# MSDriver_Ver2_0.net
KiCad netlist of a schematic drawn in EasyEDA Pro
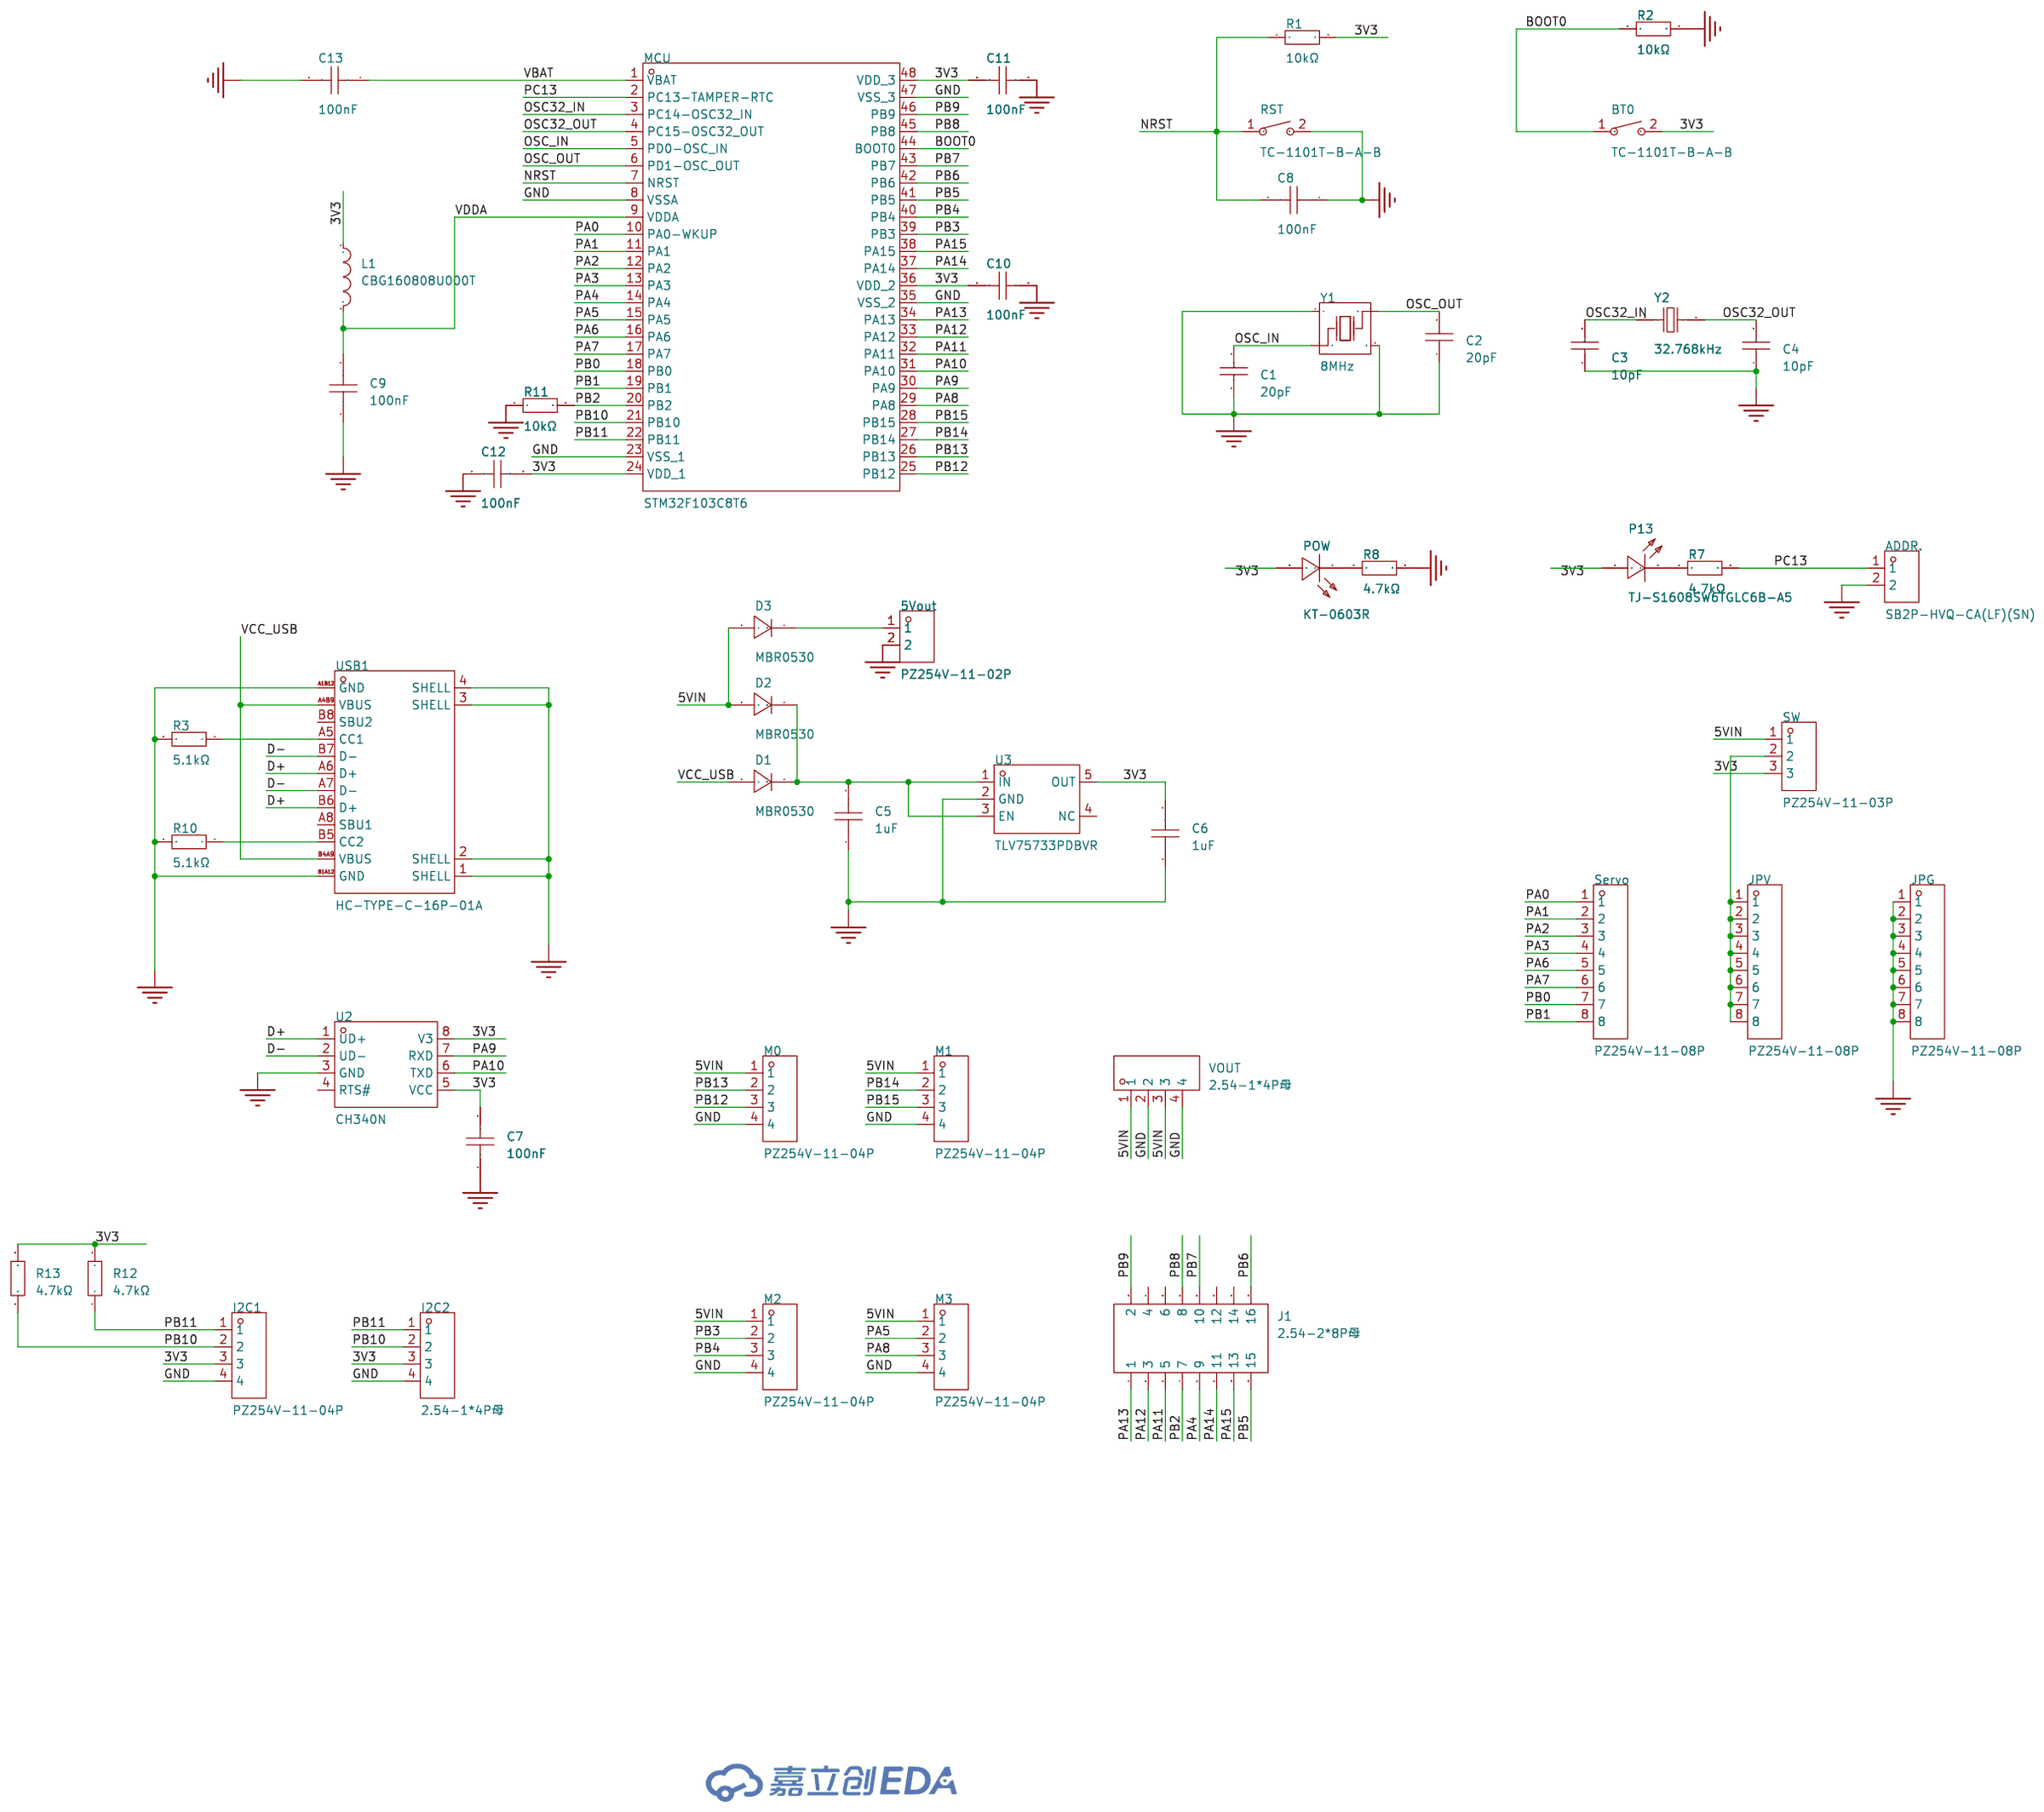
[diagram p0: schematic sheet]

(export (version "E")
  (design (tool "Eeschema 10.0.6"))
  (components
    (comp (ref "5Vout")
      (value "PZ254V-11-02P")
      (footprint "easyedapro:HDR-TH_2P-P2.54-V-M")
      (fields (field (name "Manufacturer") "XFCN(兴飞)"))
      (libsource (lib "easyedapro") (part "PZ254V-11-02P"))
    )
    (comp (ref "ADDR.")
      (value "SB2P-HVQ-CA(LF)(SN)")
      (footprint "easyedapro:HDR-TH_2P-P2.54-V-M-1")
      (fields (field (name "Manufacturer") "JST"))
      (libsource (lib "easyedapro") (part "SB2P-HVQ-CA (LF)(SN)"))
    )
    (comp (ref "BT0")
      (value "TC-1101T-B-A-B")
      (footprint "easyedapro:KEY-TH_2P-L6.0-W3.5-P6.50")
      (fields (field (name "Manufacturer") "XKB Connectivity(中国星坤)"))
      (libsource (lib "easyedapro") (part "TC-1101T-B-A-B"))
    )
    (comp (ref "C1")
      (value "20pF")
      (footprint "easyedapro:C0603")
      (description "容值:20pF;精度:±5%;额定电压:50V;材质(温度系数):C0G;")
      (fields
        (field (name "Manufacturer Part") "CL10C200JB8NNNC")
        (field (name "Manufacturer") "SAMSUNG(三星)")
      )
      (libsource (lib "easyedapro") (part "CL10C200JB8NNNC"))
    )
    (comp (ref "C2")
      (value "20pF")
      (footprint "easyedapro:C0603")
      (description "容值:20pF;精度:±5%;额定电压:50V;材质(温度系数):C0G;")
      (fields
        (field (name "Manufacturer Part") "CL10C200JB8NNNC")
        (field (name "Manufacturer") "SAMSUNG(三星)")
      )
      (libsource (lib "easyedapro") (part "CL10C200JB8NNNC"))
    )
    (comp (ref "C3")
      (value "10pF")
      (footprint "easyedapro:C0603")
      (description "容值:10pF;精度:±5%;额定电压:50V;材质(温度系数):C0G;")
      (fields
        (field (name "Manufacturer Part") "CL10C100JB8NNNC")
        (field (name "Manufacturer") "SAMSUNG(三星)")
      )
      (libsource (lib "easyedapro") (part "CL10C100JB8NNNC"))
    )
    (comp (ref "C4")
      (value "10pF")
      (footprint "easyedapro:C0603")
      (description "容值:10pF;精度:±5%;额定电压:50V;材质(温度系数):C0G;")
      (fields
        (field (name "Manufacturer Part") "CL10C100JB8NNNC")
        (field (name "Manufacturer") "SAMSUNG(三星)")
      )
      (libsource (lib "easyedapro") (part "CL10C100JB8NNNC"))
    )
    (comp (ref "C5")
      (value "1uF")
      (footprint "easyedapro:C0603")
      (description "容值:1uF;精度:±10%;额定电压:50V;材质(温度系数):X5R;")
      (fields
        (field (name "Manufacturer Part") "CL10A105KB8NNNC")
        (field (name "Manufacturer") "SAMSUNG(三星)")
      )
      (libsource (lib "easyedapro") (part "CL10A105KB8NNNC"))
    )
    (comp (ref "C6")
      (value "1uF")
      (footprint "easyedapro:C0603")
      (description "容值:1uF;精度:±10%;额定电压:50V;材质(温度系数):X5R;")
      (fields
        (field (name "Manufacturer Part") "CL10A105KB8NNNC")
        (field (name "Manufacturer") "SAMSUNG(三星)")
      )
      (libsource (lib "easyedapro") (part "CL10A105KB8NNNC"))
    )
    (comp (ref "C7")
      (value "100nF")
      (footprint "easyedapro:C0603")
      (description "容值:100nF;精度:±10%;额定电压:50V;材质(温度系数):X7R;")
      (fields
        (field (name "Manufacturer Part") "CGA0603X7R104K500JT")
        (field (name "Manufacturer") "HRE(芯声)")
      )
      (libsource (lib "easyedapro") (part "CGA0603X7R104K500JT"))
    )
    (comp (ref "C8")
      (value "100nF")
      (footprint "easyedapro:C0603")
      (description "容值:100nF;精度:±10%;额定电压:50V;材质(温度系数):X7R;")
      (fields
        (field (name "Manufacturer Part") "CGA0603X7R104K500JT")
        (field (name "Manufacturer") "HRE(芯声)")
      )
      (libsource (lib "easyedapro") (part "CGA0603X7R104K500JT"))
    )
    (comp (ref "C9")
      (value "100nF")
      (footprint "easyedapro:C0603")
      (description "容值:100nF;精度:±10%;额定电压:50V;材质(温度系数):X7R;")
      (fields
        (field (name "Manufacturer Part") "CGA0603X7R104K500JT")
        (field (name "Manufacturer") "HRE(芯声)")
      )
      (libsource (lib "easyedapro") (part "CGA0603X7R104K500JT"))
    )
    (comp (ref "C10")
      (value "100nF")
      (footprint "easyedapro:C0603")
      (description "容值:100nF;精度:±10%;额定电压:50V;材质(温度系数):X7R;")
      (fields
        (field (name "Manufacturer Part") "CGA0603X7R104K500JT")
        (field (name "Manufacturer") "HRE(芯声)")
      )
      (libsource (lib "easyedapro") (part "CGA0603X7R104K500JT"))
    )
    (comp (ref "C11")
      (value "100nF")
      (footprint "easyedapro:C0603")
      (description "容值:100nF;精度:±10%;额定电压:50V;材质(温度系数):X7R;")
      (fields
        (field (name "Manufacturer Part") "CGA0603X7R104K500JT")
        (field (name "Manufacturer") "HRE(芯声)")
      )
      (libsource (lib "easyedapro") (part "CGA0603X7R104K500JT"))
    )
    (comp (ref "C12")
      (value "100nF")
      (footprint "easyedapro:C0603")
      (description "容值:100nF;精度:±10%;额定电压:50V;材质(温度系数):X7R;")
      (fields
        (field (name "Manufacturer Part") "CGA0603X7R104K500JT")
        (field (name "Manufacturer") "HRE(芯声)")
      )
      (libsource (lib "easyedapro") (part "CGA0603X7R104K500JT"))
    )
    (comp (ref "C13")
      (value "100nF")
      (footprint "easyedapro:C0603")
      (description "容值:100nF;精度:±10%;额定电压:50V;材质(温度系数):X7R;")
      (fields
        (field (name "Manufacturer Part") "CGA0603X7R104K500JT")
        (field (name "Manufacturer") "HRE(芯声)")
      )
      (libsource (lib "easyedapro") (part "CGA0603X7R104K500JT"))
    )
    (comp (ref "D1")
      (value "MBR0530")
      (footprint "easyedapro:SOD-123_L2.8-W1.8-LS3.7-RD")
      (description "二极管配置:-;正向压降(Vf):550mV@500mA;直流反向耐压(Vr):30V;整流电流:500mA;")
      (fields (field (name "Manufacturer") "CJ(江苏长电/长晶)"))
      (libsource (lib "easyedapro") (part "MBR0530"))
    )
    (comp (ref "D2")
      (value "MBR0530")
      (footprint "easyedapro:SOD-123_L2.8-W1.8-LS3.7-RD")
      (description "二极管配置:-;正向压降(Vf):550mV@500mA;直流反向耐压(Vr):30V;整流电流:500mA;")
      (fields (field (name "Manufacturer") "CJ(江苏长电/长晶)"))
      (libsource (lib "easyedapro") (part "MBR0530"))
    )
    (comp (ref "D3")
      (value "MBR0530")
      (footprint "easyedapro:SOD-123_L2.8-W1.8-LS3.7-RD")
      (description "二极管配置:-;正向压降(Vf):550mV@500mA;直流反向耐压(Vr):30V;整流电流:500mA;")
      (fields (field (name "Manufacturer") "CJ(江苏长电/长晶)"))
      (libsource (lib "easyedapro") (part "MBR0530"))
    )
    (comp (ref "I2C1")
      (value "PZ254V-11-04P")
      (footprint "easyedapro:HDR-TH_4P-P2.54-V-M")
      (fields (field (name "Manufacturer") "XFCN(兴飞)"))
      (libsource (lib "easyedapro") (part "PZ254V-11-04P_C2691448"))
    )
    (comp (ref "I2C2")
      (value "2.54-1*4P母")
      (footprint "easyedapro:HDR-TH_4P-P2.54-V-F")
      (fields (field (name "Manufacturer") "BOOMELE(博穆精密)"))
      (libsource (lib "easyedapro") (part "2.54-1*4P母"))
    )
    (comp (ref "J1")
      (value "2.54-2*8P母")
      (footprint "easyedapro:HDR-TH_16P-P2.54-V-F-R2-C8-S2.54")
      (description "插孔结构:2x8P;间距:2.54mm;行距:2.54mm;安装类型:直插;排数:双排;总孔位数:16P;塑高:-;触头材质:黄铜;触头镀层:-;")
      (fields (field (name "Manufacturer") "BOOMELE(博穆精密)"))
      (libsource (lib "easyedapro") (part "Header-Female-2.54_2x8"))
    )
    (comp (ref "JPG")
      (value "PZ254V-11-08P")
      (footprint "easyedapro:HDR-TH_8P-P2.54-V-M")
      (fields (field (name "Manufacturer") "XFCN(兴飞)"))
      (libsource (lib "easyedapro") (part "PZ254V-11-08P"))
    )
    (comp (ref "JPV")
      (value "PZ254V-11-08P")
      (footprint "easyedapro:HDR-TH_8P-P2.54-V-M")
      (fields (field (name "Manufacturer") "XFCN(兴飞)"))
      (libsource (lib "easyedapro") (part "PZ254V-11-08P"))
    )
    (comp (ref "L1")
      (value "CBG160808U000T")
      (footprint "easyedapro:L0603")
      (description "标称阻抗@测试频率:0Ω@100MHz;直流电阻(RDC):100mΩ;")
      (fields (field (name "Manufacturer") "FH(风华)"))
      (libsource (lib "easyedapro") (part "CBG160808U000T"))
    )
    (comp (ref "M0")
      (value "PZ254V-11-04P")
      (footprint "easyedapro:HDR-TH_4P-P2.54-V-M")
      (fields (field (name "Manufacturer") "XFCN(兴飞)"))
      (libsource (lib "easyedapro") (part "PZ254V-11-04P_C2691448"))
    )
    (comp (ref "M1")
      (value "PZ254V-11-04P")
      (footprint "easyedapro:HDR-TH_4P-P2.54-V-M")
      (fields (field (name "Manufacturer") "XFCN(兴飞)"))
      (libsource (lib "easyedapro") (part "PZ254V-11-04P_C2691448"))
    )
    (comp (ref "M2")
      (value "PZ254V-11-04P")
      (footprint "easyedapro:HDR-TH_4P-P2.54-V-M")
      (fields (field (name "Manufacturer") "XFCN(兴飞)"))
      (libsource (lib "easyedapro") (part "PZ254V-11-04P_C2691448"))
    )
    (comp (ref "M3")
      (value "PZ254V-11-04P")
      (footprint "easyedapro:HDR-TH_4P-P2.54-V-M")
      (fields (field (name "Manufacturer") "XFCN(兴飞)"))
      (libsource (lib "easyedapro") (part "PZ254V-11-04P_C2691448"))
    )
    (comp (ref "MCU")
      (value "STM32F103C8T6")
      (footprint "easyedapro:LQFP-48_L7.0-W7.0-P0.50-LS9.0-BL")
      (description "CPU内核:ARM-M3;CPU最大主频:72MHz;应用领域:-;")
      (fields (field (name "Manufacturer") "ST(意法半导体)"))
      (libsource (lib "easyedapro") (part "STM32F103C8T6"))
    )
    (comp (ref "P13")
      (value "TJ-S1608SW6TGLC6B-A5")
      (footprint "easyedapro:LED0603-R-RD_BLUE")
      (description "发光颜色:蓝色;功率:111mW;正向电流:20mA;主波长:460nm;二极管配置:-;透镜颜色:无色透明透镜;色温:-;发光角度:120°;载带方式:-;工作温度:-40°C~+80°C;")
      (fields (field (name "Manufacturer") "TOGIALED(统佳)"))
      (libsource (lib "easyedapro") (part "TJ-S1608SW6TGLC6B-A5"))
    )
    (comp (ref "POW")
      (value "KT-0603R")
      (footprint "easyedapro:LED0603-RD")
      (description "发光颜色:红色;功率:-;正向电流:-;主波长:-;二极管配置:-;透镜颜色:-;色温:-;发光角度:-;载带方式:-;工作温度:-40°C~+85°C;")
      (fields (field (name "Manufacturer") "KENTO"))
      (libsource (lib "easyedapro") (part "KT-0603R"))
    )
    (comp (ref "R1")
      (value "10kΩ")
      (footprint "easyedapro:R0603")
      (fields
        (field (name "Manufacturer Part") "0603WAF1002T5E")
        (field (name "Manufacturer") "UNI-ROYAL(厚声)")
      )
      (libsource (lib "easyedapro") (part "电阻"))
    )
    (comp (ref "R2")
      (value "10kΩ")
      (footprint "easyedapro:R0603")
      (fields
        (field (name "Manufacturer Part") "0603WAF1002T5E")
        (field (name "Manufacturer") "UNI-ROYAL(厚声)")
      )
      (libsource (lib "easyedapro") (part "电阻"))
    )
    (comp (ref "R3")
      (value "5.1kΩ")
      (footprint "easyedapro:R0603")
      (fields
        (field (name "Manufacturer Part") "0603WAF5101T5E")
        (field (name "Manufacturer") "UNI-ROYAL(厚声)")
      )
      (libsource (lib "easyedapro") (part "电阻"))
    )
    (comp (ref "R7")
      (value "4.7kΩ")
      (footprint "easyedapro:R0603")
      (fields
        (field (name "Manufacturer Part") "0603WAF4701T5E")
        (field (name "Manufacturer") "UNI-ROYAL(厚声)")
      )
      (libsource (lib "easyedapro") (part "电阻"))
    )
    (comp (ref "R8")
      (value "4.7kΩ")
      (footprint "easyedapro:R0603")
      (fields
        (field (name "Manufacturer Part") "0603WAF4701T5E")
        (field (name "Manufacturer") "UNI-ROYAL(厚声)")
      )
      (libsource (lib "easyedapro") (part "电阻"))
    )
    (comp (ref "R10")
      (value "5.1kΩ")
      (footprint "easyedapro:R0603")
      (fields
        (field (name "Manufacturer Part") "0603WAF5101T5E")
        (field (name "Manufacturer") "UNI-ROYAL(厚声)")
      )
      (libsource (lib "easyedapro") (part "电阻"))
    )
    (comp (ref "R11")
      (value "10kΩ")
      (footprint "easyedapro:R0603")
      (fields
        (field (name "Manufacturer Part") "0603WAF1002T5E")
        (field (name "Manufacturer") "UNI-ROYAL(厚声)")
      )
      (libsource (lib "easyedapro") (part "电阻"))
    )
    (comp (ref "R12")
      (value "4.7kΩ")
      (footprint "easyedapro:R1206")
      (description "电阻类型:厚膜电阻;阻值:4.7kΩ;精度:±1%;功率:250mW;最大工作电压:200V;温度系数:±100ppm/°C;")
      (fields
        (field (name "Manufacturer Part") "1206W4F4701T5E")
        (field (name "Manufacturer") "UNI-ROYAL(厚声)")
      )
      (libsource (lib "easyedapro") (part "1206W4F4701T5E"))
    )
    (comp (ref "R13")
      (value "4.7kΩ")
      (footprint "easyedapro:R1206")
      (description "电阻类型:厚膜电阻;阻值:4.7kΩ;精度:±1%;功率:250mW;最大工作电压:200V;温度系数:±100ppm/°C;")
      (fields
        (field (name "Manufacturer Part") "1206W4F4701T5E")
        (field (name "Manufacturer") "UNI-ROYAL(厚声)")
      )
      (libsource (lib "easyedapro") (part "1206W4F4701T5E"))
    )
    (comp (ref "RST")
      (value "TC-1101T-B-A-B")
      (footprint "easyedapro:KEY-TH_2P-L6.0-W3.5-P6.50")
      (fields (field (name "Manufacturer") "XKB Connectivity(中国星坤)"))
      (libsource (lib "easyedapro") (part "TC-1101T-B-A-B"))
    )
    (comp (ref "Servo")
      (value "PZ254V-11-08P")
      (footprint "easyedapro:HDR-TH_8P-P2.54-V-M")
      (fields (field (name "Manufacturer") "XFCN(兴飞)"))
      (libsource (lib "easyedapro") (part "PZ254V-11-08P"))
    )
    (comp (ref "SW")
      (value "PZ254V-11-03P")
      (footprint "easyedapro:HDR-TH_3P-P2.54-V-M")
      (fields (field (name "Manufacturer") "XFCN(兴飞)"))
      (libsource (lib "easyedapro") (part "PZ254V-11-03P_C2937625"))
    )
    (comp (ref "U2")
      (value "CH340N")
      (footprint "easyedapro:SOP-8_L4.9-W3.9-P1.27-LS6.0-BL")
      (description "应用功能:USB转串口;接口协议:USB 2.0;通道数:1;数据速率:2Mbps;")
      (fields (field (name "Manufacturer") "WCH(南京沁恒)"))
      (libsource (lib "easyedapro") (part "CH340N_C2977777"))
    )
    (comp (ref "U3")
      (value "TLV75733PDBVR")
      (footprint "easyedapro:SOT-23-5_L2.9-W1.6-P0.95-LS2.8-BL")
      (description "输出类型:固定;最大输入电压:5.5V;输出电压:3.3V;输出电流:1A;电源纹波抑制比(PSRR):52dB;输出极性:正极;")
      (fields (field (name "Manufacturer") "TI(德州仪器)"))
      (libsource (lib "easyedapro") (part "TLV75733PDBVR"))
    )
    (comp (ref "USB1")
      (value "HC-TYPE-C-16P-01A")
      (footprint "easyedapro:USB-C-SMD_HC-TYPE-C-16P-01A")
      (fields (field (name "Manufacturer") "HCTL(华灿天禄)"))
      (libsource (lib "easyedapro") (part "HC-TYPE-C-16P-01A"))
    )
    (comp (ref "VOUT")
      (value "2.54-1*4P母")
      (footprint "easyedapro:HDR-TH_4P-P2.54-V-F")
      (fields (field (name "Manufacturer") "BOOMELE(博穆精密)"))
      (libsource (lib "easyedapro") (part "2.54-1*4P母"))
    )
    (comp (ref "Y1")
      (value "8MHz")
      (footprint "easyedapro:CRYSTAL-SMD_4P-L3.2-W2.5-BL")
      (description "晶振类型:贴片晶振;频率:8MHz;常温频差:±10ppm;负载电容:10pF;频率稳定度(全温):±15ppm;")
      (fields (field (name "Manufacturer Part") "TAXM8M4RDBCCT2T") (field (name "Manufacturer") "YJX(雅晶鑫)"))
      (libsource (lib "easyedapro") (part "TAXM8M4RDBCCT2T"))
    )
    (comp (ref "Y2")
      (value "32.768kHz")
      (footprint "easyedapro:FC-135R_L3.2-W1.5")
      (description "晶振类型:贴片晶振;频率:32.768kHz;常温频差:±20ppm;负载电容:12.5pF;")
      (fields (field (name "Manufacturer Part") "Q13FC13500004") (field (name "Manufacturer") "EPSON(爱普生)"))
      (libsource (lib "easyedapro") (part "Q13FC1350000400"))
    )
  )
  (nets
    (net (code "1") (name "/3V3") (class "Default")
      (node (ref "BT0") (pin "2") (pinfunction "2_2") (pintype "unspecified"))
      (node (ref "C10") (pin "1") (pinfunction "1_1") (pintype "unspecified"))
      (node (ref "C11") (pin "1") (pinfunction "1_1") (pintype "unspecified"))
      (node (ref "C12") (pin "2") (pinfunction "2_2") (pintype "unspecified"))
      (node (ref "C6") (pin "2") (pinfunction "2_2") (pintype "unspecified"))
      (node (ref "C7") (pin "2") (pinfunction "2_2") (pintype "unspecified"))
      (node (ref "I2C1") (pin "3") (pinfunction "3_3") (pintype "unspecified"))
      (node (ref "I2C2") (pin "3") (pinfunction "3_3") (pintype "unspecified"))
      (node (ref "L1") (pin "1") (pinfunction "1_1") (pintype "unspecified"))
      (node (ref "MCU") (pin "24") (pinfunction "VDD_1_24") (pintype "unspecified"))
      (node (ref "MCU") (pin "36") (pinfunction "VDD_2_36") (pintype "unspecified"))
      (node (ref "MCU") (pin "48") (pinfunction "VDD_3_48") (pintype "unspecified"))
      (node (ref "P13") (pin "1") (pinfunction "A_1") (pintype "unspecified"))
      (node (ref "POW") (pin "2") (pinfunction "A_2") (pintype "unspecified"))
      (node (ref "R1") (pin "2") (pinfunction "2_2") (pintype "input"))
      (node (ref "R12") (pin "2") (pinfunction "2_2") (pintype "input"))
      (node (ref "R13") (pin "2") (pinfunction "2_2") (pintype "input"))
      (node (ref "SW") (pin "3") (pinfunction "3_3") (pintype "unspecified"))
      (node (ref "U2") (pin "5") (pinfunction "VCC_5") (pintype "unspecified"))
      (node (ref "U2") (pin "8") (pinfunction "V3_8") (pintype "unspecified"))
      (node (ref "U3") (pin "5") (pinfunction "OUT_5") (pintype "unspecified"))
    )
    (net (code "2") (name "/5VIN") (class "Default")
      (node (ref "D2") (pin "2") (pinfunction "A_2") (pintype "unspecified"))
      (node (ref "D3") (pin "2") (pinfunction "A_2") (pintype "unspecified"))
      (node (ref "M0") (pin "1") (pinfunction "1_1") (pintype "unspecified"))
      (node (ref "M1") (pin "1") (pinfunction "1_1") (pintype "unspecified"))
      (node (ref "M2") (pin "1") (pinfunction "1_1") (pintype "unspecified"))
      (node (ref "M3") (pin "1") (pinfunction "1_1") (pintype "unspecified"))
      (node (ref "SW") (pin "1") (pinfunction "1_1") (pintype "unspecified"))
      (node (ref "VOUT") (pin "1") (pinfunction "1_1") (pintype "unspecified"))
      (node (ref "VOUT") (pin "3") (pinfunction "3_3") (pintype "unspecified"))
    )
    (net (code "3") (name "/BOOT0") (class "Default")
      (node (ref "BT0") (pin "1") (pinfunction "1_1") (pintype "unspecified"))
      (node (ref "MCU") (pin "44") (pinfunction "BOOT0_44") (pintype "unspecified"))
      (node (ref "R2") (pin "1") (pinfunction "1_1") (pintype "input"))
    )
    (net (code "4") (name "/D+") (class "Default")
      (node (ref "U2") (pin "1") (pinfunction "UD+_1") (pintype "unspecified"))
      (node (ref "USB1") (pin "A6") (pinfunction "D+_A6") (pintype "unspecified"))
      (node (ref "USB1") (pin "B6") (pinfunction "D+_B6") (pintype "unspecified"))
    )
    (net (code "5") (name "/D-") (class "Default")
      (node (ref "U2") (pin "2") (pinfunction "UD-_2") (pintype "unspecified"))
      (node (ref "USB1") (pin "A7") (pinfunction "D-_A7") (pintype "unspecified"))
      (node (ref "USB1") (pin "B7") (pinfunction "D-_B7") (pintype "unspecified"))
    )
    (net (code "6") (name "/NRST") (class "Default")
      (node (ref "C8") (pin "2") (pinfunction "2_2") (pintype "unspecified"))
      (node (ref "MCU") (pin "7") (pinfunction "NRST_7") (pintype "unspecified"))
      (node (ref "R1") (pin "1") (pinfunction "1_1") (pintype "input"))
      (node (ref "RST") (pin "1") (pinfunction "1_1") (pintype "unspecified"))
    )
    (net (code "7") (name "/OSC32_IN") (class "Default")
      (node (ref "C3") (pin "2") (pinfunction "2_2") (pintype "input"))
      (node (ref "MCU") (pin "3") (pinfunction "PC14-OSC32_IN_3") (pintype "unspecified"))
      (node (ref "Y2") (pin "1") (pinfunction "1_1") (pintype "unspecified"))
    )
    (net (code "8") (name "/OSC32_OUT") (class "Default")
      (node (ref "C4") (pin "2") (pinfunction "2_2") (pintype "input"))
      (node (ref "MCU") (pin "4") (pinfunction "PC15-OSC32_OUT_4") (pintype "unspecified"))
      (node (ref "Y2") (pin "2") (pinfunction "2_2") (pintype "unspecified"))
    )
    (net (code "9") (name "/OSC_IN") (class "Default")
      (node (ref "C1") (pin "2") (pinfunction "2_2") (pintype "input"))
      (node (ref "MCU") (pin "5") (pinfunction "PD0-OSC_IN_5") (pintype "unspecified"))
      (node (ref "Y1") (pin "1") (pinfunction "1_1") (pintype "input"))
    )
    (net (code "10") (name "/OSC_OUT") (class "Default")
      (node (ref "C2") (pin "2") (pinfunction "2_2") (pintype "input"))
      (node (ref "MCU") (pin "6") (pinfunction "PD1-OSC_OUT_6") (pintype "unspecified"))
      (node (ref "Y1") (pin "3") (pinfunction "3_3") (pintype "input"))
    )
    (net (code "11") (name "/PA0") (class "Default")
      (node (ref "MCU") (pin "10") (pinfunction "PA0-WKUP_10") (pintype "unspecified"))
      (node (ref "Servo") (pin "1") (pinfunction "1_1") (pintype "unspecified"))
    )
    (net (code "12") (name "/PA1") (class "Default")
      (node (ref "MCU") (pin "11") (pinfunction "PA1_11") (pintype "unspecified"))
      (node (ref "Servo") (pin "2") (pinfunction "2_2") (pintype "unspecified"))
    )
    (net (code "13") (name "/PA2") (class "Default")
      (node (ref "MCU") (pin "12") (pinfunction "PA2_12") (pintype "unspecified"))
      (node (ref "Servo") (pin "3") (pinfunction "3_3") (pintype "unspecified"))
    )
    (net (code "14") (name "/PA3") (class "Default")
      (node (ref "MCU") (pin "13") (pinfunction "PA3_13") (pintype "unspecified"))
      (node (ref "Servo") (pin "4") (pinfunction "4_4") (pintype "unspecified"))
    )
    (net (code "15") (name "/PA4") (class "Default")
      (node (ref "J1") (pin "9") (pinfunction "9_9") (pintype "input"))
      (node (ref "MCU") (pin "14") (pinfunction "PA4_14") (pintype "unspecified"))
    )
    (net (code "16") (name "/PA5") (class "Default")
      (node (ref "M3") (pin "2") (pinfunction "2_2") (pintype "unspecified"))
      (node (ref "MCU") (pin "15") (pinfunction "PA5_15") (pintype "unspecified"))
    )
    (net (code "17") (name "/PA6") (class "Default")
      (node (ref "MCU") (pin "16") (pinfunction "PA6_16") (pintype "unspecified"))
      (node (ref "Servo") (pin "5") (pinfunction "5_5") (pintype "unspecified"))
    )
    (net (code "18") (name "/PA7") (class "Default")
      (node (ref "MCU") (pin "17") (pinfunction "PA7_17") (pintype "unspecified"))
      (node (ref "Servo") (pin "6") (pinfunction "6_6") (pintype "unspecified"))
    )
    (net (code "19") (name "/PA8") (class "Default")
      (node (ref "M3") (pin "3") (pinfunction "3_3") (pintype "unspecified"))
      (node (ref "MCU") (pin "29") (pinfunction "PA8_29") (pintype "unspecified"))
    )
    (net (code "20") (name "/PA9") (class "Default")
      (node (ref "MCU") (pin "30") (pinfunction "PA9_30") (pintype "unspecified"))
      (node (ref "U2") (pin "7") (pinfunction "RXD_7") (pintype "unspecified"))
    )
    (net (code "21") (name "/PA10") (class "Default")
      (node (ref "MCU") (pin "31") (pinfunction "PA10_31") (pintype "unspecified"))
      (node (ref "U2") (pin "6") (pinfunction "TXD_6") (pintype "unspecified"))
    )
    (net (code "22") (name "/PA11") (class "Default")
      (node (ref "J1") (pin "5") (pinfunction "5_5") (pintype "input"))
      (node (ref "MCU") (pin "32") (pinfunction "PA11_32") (pintype "unspecified"))
    )
    (net (code "23") (name "/PA12") (class "Default")
      (node (ref "J1") (pin "3") (pinfunction "3_3") (pintype "input"))
      (node (ref "MCU") (pin "33") (pinfunction "PA12_33") (pintype "unspecified"))
    )
    (net (code "24") (name "/PA13") (class "Default")
      (node (ref "J1") (pin "1") (pinfunction "1_1") (pintype "input"))
      (node (ref "MCU") (pin "34") (pinfunction "PA13_34") (pintype "unspecified"))
    )
    (net (code "25") (name "/PA14") (class "Default")
      (node (ref "J1") (pin "11") (pinfunction "11_11") (pintype "input"))
      (node (ref "MCU") (pin "37") (pinfunction "PA14_37") (pintype "unspecified"))
    )
    (net (code "26") (name "/PA15") (class "Default")
      (node (ref "J1") (pin "13") (pinfunction "13_13") (pintype "input"))
      (node (ref "MCU") (pin "38") (pinfunction "PA15_38") (pintype "unspecified"))
    )
    (net (code "27") (name "/PB0") (class "Default")
      (node (ref "MCU") (pin "18") (pinfunction "PB0_18") (pintype "unspecified"))
      (node (ref "Servo") (pin "7") (pinfunction "7_7") (pintype "unspecified"))
    )
    (net (code "28") (name "/PB1") (class "Default")
      (node (ref "MCU") (pin "19") (pinfunction "PB1_19") (pintype "unspecified"))
      (node (ref "Servo") (pin "8") (pinfunction "8_8") (pintype "unspecified"))
    )
    (net (code "29") (name "/PB2") (class "Default")
      (node (ref "J1") (pin "7") (pinfunction "7_7") (pintype "input"))
      (node (ref "MCU") (pin "20") (pinfunction "PB2_20") (pintype "unspecified"))
      (node (ref "R11") (pin "2") (pinfunction "2_2") (pintype "input"))
    )
    (net (code "30") (name "/PB3") (class "Default")
      (node (ref "M2") (pin "2") (pinfunction "2_2") (pintype "unspecified"))
      (node (ref "MCU") (pin "39") (pinfunction "PB3_39") (pintype "unspecified"))
    )
    (net (code "31") (name "/PB4") (class "Default")
      (node (ref "M2") (pin "3") (pinfunction "3_3") (pintype "unspecified"))
      (node (ref "MCU") (pin "40") (pinfunction "PB4_40") (pintype "unspecified"))
    )
    (net (code "32") (name "/PB5") (class "Default")
      (node (ref "J1") (pin "15") (pinfunction "15_15") (pintype "input"))
      (node (ref "MCU") (pin "41") (pinfunction "PB5_41") (pintype "unspecified"))
    )
    (net (code "33") (name "/PB6") (class "Default")
      (node (ref "J1") (pin "16") (pinfunction "16_16") (pintype "input"))
      (node (ref "MCU") (pin "42") (pinfunction "PB6_42") (pintype "unspecified"))
    )
    (net (code "34") (name "/PB7") (class "Default")
      (node (ref "J1") (pin "10") (pinfunction "10_10") (pintype "input"))
      (node (ref "MCU") (pin "43") (pinfunction "PB7_43") (pintype "unspecified"))
    )
    (net (code "35") (name "/PB8") (class "Default")
      (node (ref "J1") (pin "8") (pinfunction "8_8") (pintype "input"))
      (node (ref "MCU") (pin "45") (pinfunction "PB8_45") (pintype "unspecified"))
    )
    (net (code "36") (name "/PB9") (class "Default")
      (node (ref "J1") (pin "2") (pinfunction "2_2") (pintype "input"))
      (node (ref "MCU") (pin "46") (pinfunction "PB9_46") (pintype "unspecified"))
    )
    (net (code "37") (name "/PB10") (class "Default")
      (node (ref "I2C1") (pin "2") (pinfunction "2_2") (pintype "unspecified"))
      (node (ref "I2C2") (pin "2") (pinfunction "2_2") (pintype "unspecified"))
      (node (ref "MCU") (pin "21") (pinfunction "PB10_21") (pintype "unspecified"))
      (node (ref "R13") (pin "1") (pinfunction "1_1") (pintype "input"))
    )
    (net (code "38") (name "/PB11") (class "Default")
      (node (ref "I2C1") (pin "1") (pinfunction "1_1") (pintype "unspecified"))
      (node (ref "I2C2") (pin "1") (pinfunction "1_1") (pintype "unspecified"))
      (node (ref "MCU") (pin "22") (pinfunction "PB11_22") (pintype "unspecified"))
      (node (ref "R12") (pin "1") (pinfunction "1_1") (pintype "input"))
    )
    (net (code "39") (name "/PB12") (class "Default")
      (node (ref "M0") (pin "3") (pinfunction "3_3") (pintype "unspecified"))
      (node (ref "MCU") (pin "25") (pinfunction "PB12_25") (pintype "unspecified"))
    )
    (net (code "40") (name "/PB13") (class "Default")
      (node (ref "M0") (pin "2") (pinfunction "2_2") (pintype "unspecified"))
      (node (ref "MCU") (pin "26") (pinfunction "PB13_26") (pintype "unspecified"))
    )
    (net (code "41") (name "/PB14") (class "Default")
      (node (ref "M1") (pin "2") (pinfunction "2_2") (pintype "unspecified"))
      (node (ref "MCU") (pin "27") (pinfunction "PB14_27") (pintype "unspecified"))
    )
    (net (code "42") (name "/PB15") (class "Default")
      (node (ref "M1") (pin "3") (pinfunction "3_3") (pintype "unspecified"))
      (node (ref "MCU") (pin "28") (pinfunction "PB15_28") (pintype "unspecified"))
    )
    (net (code "43") (name "/PC13") (class "Default")
      (node (ref "ADDR.") (pin "1") (pinfunction "1_1") (pintype "unspecified"))
      (node (ref "MCU") (pin "2") (pinfunction "PC13-TAMPER-RTC_2") (pintype "unspecified"))
      (node (ref "R7") (pin "2") (pinfunction "2_2") (pintype "input"))
    )
    (net (code "44") (name "/VBAT") (class "Default")
      (node (ref "C13") (pin "1") (pinfunction "1_1") (pintype "unspecified"))
      (node (ref "MCU") (pin "1") (pinfunction "VBAT_1") (pintype "unspecified"))
    )
    (net (code "45") (name "/VCC_USB") (class "Default")
      (node (ref "D1") (pin "2") (pinfunction "A_2") (pintype "unspecified"))
      (node (ref "USB1") (pin "A4B9") (pinfunction "VBUS_A4B9") (pintype "unspecified"))
      (node (ref "USB1") (pin "B4A9") (pinfunction "VBUS_B4A9") (pintype "unspecified"))
    )
    (net (code "46") (name "/VDDA") (class "Default")
      (node (ref "C9") (pin "2") (pinfunction "2_2") (pintype "unspecified"))
      (node (ref "L1") (pin "2") (pinfunction "2_2") (pintype "unspecified"))
      (node (ref "MCU") (pin "9") (pinfunction "VDDA_9") (pintype "unspecified"))
    )
    (net (code "47") (name "GND") (class "Default")
      (node (ref "5Vout") (pin "2") (pinfunction "2_2") (pintype "unspecified"))
      (node (ref "ADDR.") (pin "2") (pinfunction "2_2") (pintype "unspecified"))
      (node (ref "C1") (pin "1") (pinfunction "1_1") (pintype "input"))
      (node (ref "C10") (pin "2") (pinfunction "2_2") (pintype "unspecified"))
      (node (ref "C11") (pin "2") (pinfunction "2_2") (pintype "unspecified"))
      (node (ref "C12") (pin "1") (pinfunction "1_1") (pintype "unspecified"))
      (node (ref "C13") (pin "2") (pinfunction "2_2") (pintype "unspecified"))
      (node (ref "C2") (pin "1") (pinfunction "1_1") (pintype "input"))
      (node (ref "C3") (pin "1") (pinfunction "1_1") (pintype "input"))
      (node (ref "C4") (pin "1") (pinfunction "1_1") (pintype "input"))
      (node (ref "C5") (pin "1") (pinfunction "1_1") (pintype "unspecified"))
      (node (ref "C6") (pin "1") (pinfunction "1_1") (pintype "unspecified"))
      (node (ref "C7") (pin "1") (pinfunction "1_1") (pintype "unspecified"))
      (node (ref "C8") (pin "1") (pinfunction "1_1") (pintype "unspecified"))
      (node (ref "C9") (pin "1") (pinfunction "1_1") (pintype "unspecified"))
      (node (ref "I2C1") (pin "4") (pinfunction "4_4") (pintype "unspecified"))
      (node (ref "I2C2") (pin "4") (pinfunction "4_4") (pintype "unspecified"))
      (node (ref "JPG") (pin "1") (pinfunction "1_1") (pintype "unspecified"))
      (node (ref "JPG") (pin "2") (pinfunction "2_2") (pintype "unspecified"))
      (node (ref "JPG") (pin "3") (pinfunction "3_3") (pintype "unspecified"))
      (node (ref "JPG") (pin "4") (pinfunction "4_4") (pintype "unspecified"))
      (node (ref "JPG") (pin "5") (pinfunction "5_5") (pintype "unspecified"))
      (node (ref "JPG") (pin "6") (pinfunction "6_6") (pintype "unspecified"))
      (node (ref "JPG") (pin "7") (pinfunction "7_7") (pintype "unspecified"))
      (node (ref "JPG") (pin "8") (pinfunction "8_8") (pintype "unspecified"))
      (node (ref "M0") (pin "4") (pinfunction "4_4") (pintype "unspecified"))
      (node (ref "M1") (pin "4") (pinfunction "4_4") (pintype "unspecified"))
      (node (ref "M2") (pin "4") (pinfunction "4_4") (pintype "unspecified"))
      (node (ref "M3") (pin "4") (pinfunction "4_4") (pintype "unspecified"))
      (node (ref "MCU") (pin "23") (pinfunction "VSS_1_23") (pintype "unspecified"))
      (node (ref "MCU") (pin "35") (pinfunction "VSS_2_35") (pintype "unspecified"))
      (node (ref "MCU") (pin "47") (pinfunction "VSS_3_47") (pintype "unspecified"))
      (node (ref "MCU") (pin "8") (pinfunction "VSSA_8") (pintype "unspecified"))
      (node (ref "R10") (pin "2") (pinfunction "2_2") (pintype "input"))
      (node (ref "R11") (pin "1") (pinfunction "1_1") (pintype "input"))
      (node (ref "R2") (pin "2") (pinfunction "2_2") (pintype "input"))
      (node (ref "R3") (pin "2") (pinfunction "2_2") (pintype "input"))
      (node (ref "R8") (pin "2") (pinfunction "2_2") (pintype "input"))
      (node (ref "RST") (pin "2") (pinfunction "2_2") (pintype "unspecified"))
      (node (ref "U2") (pin "3") (pinfunction "GND_3") (pintype "unspecified"))
      (node (ref "U3") (pin "2") (pinfunction "GND_2") (pintype "unspecified"))
      (node (ref "USB1") (pin "1") (pinfunction "SHELL_1") (pintype "unspecified"))
      (node (ref "USB1") (pin "2") (pinfunction "SHELL_2") (pintype "unspecified"))
      (node (ref "USB1") (pin "3") (pinfunction "SHELL_3") (pintype "unspecified"))
      (node (ref "USB1") (pin "4") (pinfunction "SHELL_4") (pintype "unspecified"))
      (node (ref "USB1") (pin "A1B12") (pinfunction "GND_A1B12") (pintype "unspecified"))
      (node (ref "USB1") (pin "B1A12") (pinfunction "GND_B1A12") (pintype "unspecified"))
      (node (ref "VOUT") (pin "2") (pinfunction "2_2") (pintype "unspecified"))
      (node (ref "VOUT") (pin "4") (pinfunction "4_4") (pintype "unspecified"))
      (node (ref "Y1") (pin "2") (pinfunction "2_2") (pintype "input"))
      (node (ref "Y1") (pin "4") (pinfunction "4_4") (pintype "input"))
    )
    (net (code "48") (name "Net-(D1-C)") (class "Default")
      (node (ref "C5") (pin "2") (pinfunction "2_2") (pintype "unspecified"))
      (node (ref "D1") (pin "1") (pinfunction "C_1") (pintype "unspecified"))
      (node (ref "D2") (pin "1") (pinfunction "C_1") (pintype "unspecified"))
      (node (ref "U3") (pin "1") (pinfunction "IN_1") (pintype "unspecified"))
      (node (ref "U3") (pin "3") (pinfunction "EN_3") (pintype "unspecified"))
    )
    (net (code "49") (name "Net-(D3-C)") (class "Default")
      (node (ref "5Vout") (pin "1") (pinfunction "1_1") (pintype "unspecified"))
      (node (ref "D3") (pin "1") (pinfunction "C_1") (pintype "unspecified"))
    )
    (net (code "50") (name "Net-(JPV-Pad1)") (class "Default")
      (node (ref "JPV") (pin "1") (pinfunction "1_1") (pintype "unspecified"))
      (node (ref "JPV") (pin "2") (pinfunction "2_2") (pintype "unspecified"))
      (node (ref "JPV") (pin "3") (pinfunction "3_3") (pintype "unspecified"))
      (node (ref "JPV") (pin "4") (pinfunction "4_4") (pintype "unspecified"))
      (node (ref "JPV") (pin "5") (pinfunction "5_5") (pintype "unspecified"))
      (node (ref "JPV") (pin "6") (pinfunction "6_6") (pintype "unspecified"))
      (node (ref "JPV") (pin "7") (pinfunction "7_7") (pintype "unspecified"))
      (node (ref "JPV") (pin "8") (pinfunction "8_8") (pintype "unspecified"))
      (node (ref "SW") (pin "2") (pinfunction "2_2") (pintype "unspecified"))
    )
    (net (code "51") (name "Net-(P13-K)") (class "Default")
      (node (ref "P13") (pin "2") (pinfunction "K_2") (pintype "unspecified"))
      (node (ref "R7") (pin "1") (pinfunction "1_1") (pintype "input"))
    )
    (net (code "52") (name "Net-(POW-K)") (class "Default")
      (node (ref "POW") (pin "1") (pinfunction "K_1") (pintype "unspecified"))
      (node (ref "R8") (pin "1") (pinfunction "1_1") (pintype "input"))
    )
    (net (code "53") (name "Net-(USB1-CC1)") (class "Default")
      (node (ref "R3") (pin "1") (pinfunction "1_1") (pintype "input"))
      (node (ref "USB1") (pin "A5") (pinfunction "CC1_A5") (pintype "unspecified"))
    )
    (net (code "54") (name "Net-(USB1-CC2)") (class "Default")
      (node (ref "R10") (pin "1") (pinfunction "1_1") (pintype "input"))
      (node (ref "USB1") (pin "B5") (pinfunction "CC2_B5") (pintype "unspecified"))
    )
    (net (code "55") (name "unconnected-(J1-Pad4)") (class "Default")
      (node (ref "J1") (pin "4") (pinfunction "4_4") (pintype "input"))
    )
    (net (code "56") (name "unconnected-(J1-Pad6)") (class "Default")
      (node (ref "J1") (pin "6") (pinfunction "6_6") (pintype "input"))
    )
    (net (code "57") (name "unconnected-(J1-Pad12)") (class "Default")
      (node (ref "J1") (pin "12") (pinfunction "12_12") (pintype "input"))
    )
    (net (code "58") (name "unconnected-(J1-Pad14)") (class "Default")
      (node (ref "J1") (pin "14") (pinfunction "14_14") (pintype "input"))
    )
    (net (code "59") (name "unconnected-(U2-RTS#-Pad4)") (class "Default")
      (node (ref "U2") (pin "4") (pinfunction "RTS#_4") (pintype "unspecified"))
    )
    (net (code "60") (name "unconnected-(U3-NC-Pad4)") (class "Default")
      (node (ref "U3") (pin "4") (pinfunction "NC_4") (pintype "unspecified"))
    )
    (net (code "61") (name "unconnected-(USB1-SBU1-PadA8)") (class "Default")
      (node (ref "USB1") (pin "A8") (pinfunction "SBU1_A8") (pintype "unspecified"))
    )
    (net (code "62") (name "unconnected-(USB1-SBU2-PadB8)") (class "Default")
      (node (ref "USB1") (pin "B8") (pinfunction "SBU2_B8") (pintype "unspecified"))
    )
  )
)
